# NFCUnlocker.net
KiCad netlist of a schematic drawn in EAGLE
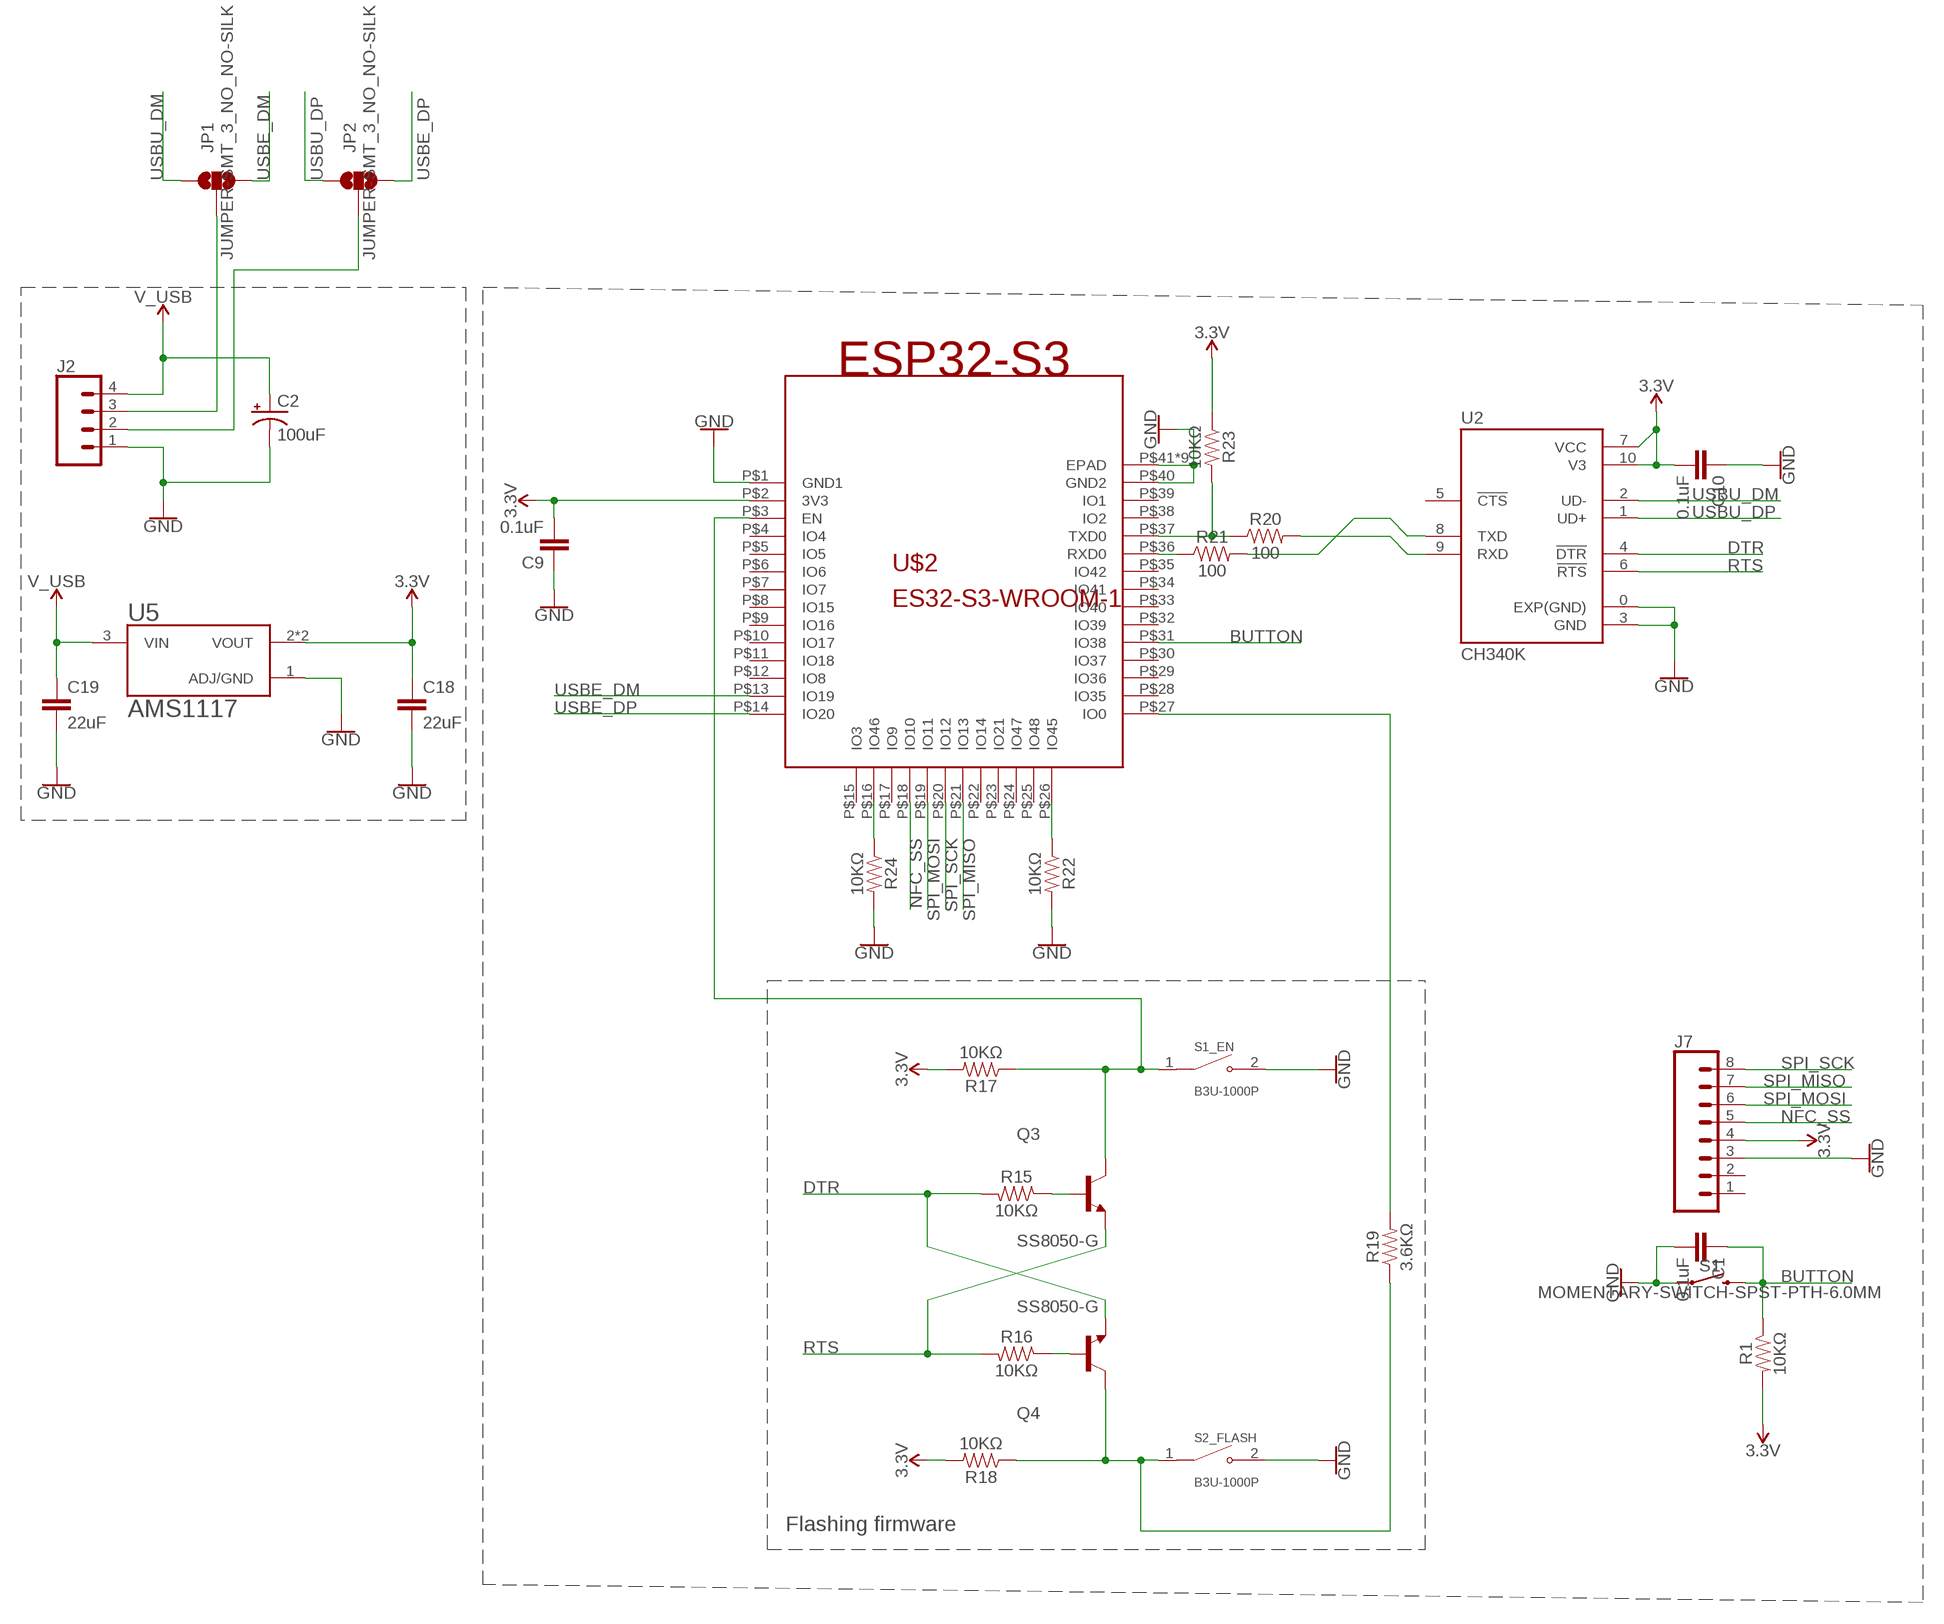
[diagram p0: schematic, sheet 1]

(export (version "E")
  (design (tool "Eeschema 10.0.6"))
  (components
    (comp (ref "C1")
      (value "0.1uF")
      (footprint "eagle-import:0402")
      (libsource (lib "eagle-import") (part "0.1UF-0402-6.3V-10%-X7R"))
    )
    (comp (ref "C2")
      (value "100uF")
      (footprint "eagle-import:CPOL-RADIAL-2.5MM-6.5MM")
      (libsource (lib "eagle-import") (part "100UF-POLAR-RADIAL-2.5MM-25V-20%"))
    )
    (comp (ref "C9")
      (value "0.1uF")
      (footprint "eagle-import:0402")
      (libsource (lib "eagle-import") (part "0.1UF-0402-6.3V-10%-X7R"))
    )
    (comp (ref "C10")
      (value "0.1uF")
      (footprint "eagle-import:0402")
      (libsource (lib "eagle-import") (part "0.1UF-0402-6.3V-10%-X7R"))
    )
    (comp (ref "C18")
      (value "22uF")
      (footprint "eagle-import:1206")
      (libsource (lib "eagle-import") (part "22UF-1206-50V-10%"))
    )
    (comp (ref "C19")
      (value "22uF")
      (footprint "eagle-import:1206")
      (libsource (lib "eagle-import") (part "22UF-1206-50V-10%"))
    )
    (comp (ref "J2")
      (value "CONN_04LONGPADS")
      (footprint "eagle-import:1X04_LONGPADS")
      (libsource (lib "eagle-import") (part "CONN_04LONGPADS"))
    )
    (comp (ref "J7")
      (value "CONN_08LONGPADS")
      (footprint "eagle-import:1X08_LONGPADS")
      (libsource (lib "eagle-import") (part "CONN_08LONGPADS"))
    )
    (comp (ref "JP1")
      (value "JUMPER-SMT_3_NO_NO-SILK")
      (footprint "eagle-import:SMT-JUMPER_3_NO_NO-SILK")
      (libsource (lib "eagle-import") (part "JUMPER-SMT_3_NO_NO-SILK"))
    )
    (comp (ref "JP2")
      (value "JUMPER-SMT_3_NO_NO-SILK")
      (footprint "eagle-import:SMT-JUMPER_3_NO_NO-SILK")
      (libsource (lib "eagle-import") (part "JUMPER-SMT_3_NO_NO-SILK"))
    )
    (comp (ref "Q3")
      (value "SS8050-G")
      (footprint "eagle-import:TRANS_SS8050-G")
      (fields (field (name "MF") "Comchip Technology"))
      (libsource (lib "eagle-import") (part "SS8050-G"))
    )
    (comp (ref "Q4")
      (value "SS8050-G")
      (footprint "eagle-import:TRANS_SS8050-G")
      (fields (field (name "MF") "Comchip Technology"))
      (libsource (lib "eagle-import") (part "SS8050-G"))
    )
    (comp (ref "R1")
      (value "10KΩ")
      (footprint "eagle-import:0402-TIGHT")
      (libsource (lib "eagle-import") (part "10KOHM-0402T-1/16W-1%"))
    )
    (comp (ref "R15")
      (value "10KΩ")
      (footprint "eagle-import:0402-TIGHT")
      (libsource (lib "eagle-import") (part "10KOHM-0402T-1/16W-1%"))
    )
    (comp (ref "R16")
      (value "10KΩ")
      (footprint "eagle-import:0402-TIGHT")
      (libsource (lib "eagle-import") (part "10KOHM-0402T-1/16W-1%"))
    )
    (comp (ref "R17")
      (value "10KΩ")
      (footprint "eagle-import:0402-TIGHT")
      (libsource (lib "eagle-import") (part "10KOHM-0402T-1/16W-1%"))
    )
    (comp (ref "R18")
      (value "10KΩ")
      (footprint "eagle-import:0402-TIGHT")
      (libsource (lib "eagle-import") (part "10KOHM-0402T-1/16W-1%"))
    )
    (comp (ref "R19")
      (value "3.6KΩ")
      (footprint "eagle-import:0402-TIGHT")
      (libsource (lib "eagle-import") (part "10KOHM-0402T-1/16W-1%"))
    )
    (comp (ref "R20")
      (value "100")
      (footprint "eagle-import:0402-TIGHT")
      (libsource (lib "eagle-import") (part "100OHM-0402-TIGHT-1/16W-1%"))
    )
    (comp (ref "R21")
      (value "100")
      (footprint "eagle-import:0402-TIGHT")
      (libsource (lib "eagle-import") (part "100OHM-0402-TIGHT-1/16W-1%"))
    )
    (comp (ref "R22")
      (value "10KΩ")
      (footprint "eagle-import:0402-TIGHT")
      (libsource (lib "eagle-import") (part "10KOHM-0402T-1/16W-1%"))
    )
    (comp (ref "R23")
      (value "10KΩ")
      (footprint "eagle-import:0402-TIGHT")
      (libsource (lib "eagle-import") (part "10KOHM-0402T-1/16W-1%"))
    )
    (comp (ref "R24")
      (value "10KΩ")
      (footprint "eagle-import:0402-TIGHT")
      (libsource (lib "eagle-import") (part "10KOHM-0402T-1/16W-1%"))
    )
    (comp (ref "S1")
      (value "MOMENTARY-SWITCH-SPST-PTH-6.0MM")
      (footprint "eagle-import:TACTILE_SWITCH_PTH_6.0MM")
      (libsource (lib "eagle-import") (part "MOMENTARY-SWITCH-SPST-PTH-6.0MM"))
    )
    (comp (ref "S1_EN")
      (value "B3U-1000P")
      (footprint "eagle-import:SW_B3U-1000P")
      (fields (field (name "MF") "Omron"))
      (libsource (lib "eagle-import") (part "B3U-1000P"))
    )
    (comp (ref "S2_FLASH")
      (value "B3U-1000P")
      (footprint "eagle-import:SW_B3U-1000P")
      (fields (field (name "MF") "Omron"))
      (libsource (lib "eagle-import") (part "B3U-1000P"))
    )
    (comp (ref "U$2")
      (value "ES32-S3-WROOM-1")
      (footprint "eagle-import:ESP32-S3-WROOM-1")
      (libsource (lib "eagle-import") (part "ES32-S3-WROOM-1"))
    )
    (comp (ref "U2")
      (value "CH340K")
      (footprint "eagle-import:SOP100P600X160-11N")
      (fields (field (name "MF") "WCH"))
      (libsource (lib "eagle-import") (part "CH340K"))
    )
    (comp (ref "U5")
      (value "AMS1117")
      (footprint "eagle-import:SOT229P700X180-4N")
      (fields (field (name "MF") "Advanced Monolithic Systems"))
      (libsource (lib "eagle-import") (part "AMS1117"))
    )
  )
  (nets
    (net (code "1") (name "/BUTTON") (class "Default")
      (node (ref "C1") (pin "1") (pinfunction "1_1") (pintype "passive"))
      (node (ref "R1") (pin "1") (pinfunction "1_1") (pintype "passive"))
      (node (ref "S1") (pin "3") (pinfunction "2_3") (pintype "passive"))
      (node (ref "U$2") (pin "P$31") (pinfunction "IO38_P$31") (pintype "bidirectional"))
    )
    (net (code "2") (name "/DTR") (class "Default")
      (node (ref "Q4") (pin "2") (pinfunction "E_2") (pintype "passive"))
      (node (ref "R15") (pin "2") (pinfunction "2_2") (pintype "passive"))
      (node (ref "U2") (pin "4") (pinfunction "~{DTR}_4") (pintype "output"))
    )
    (net (code "3") (name "/NFC_SS") (class "Default")
      (node (ref "J7") (pin "5") (pinfunction "5_5") (pintype "passive"))
      (node (ref "U$2") (pin "P$18") (pinfunction "IO10_P$18") (pintype "bidirectional"))
    )
    (net (code "4") (name "/RTS") (class "Default")
      (node (ref "Q3") (pin "2") (pinfunction "E_2") (pintype "passive"))
      (node (ref "R16") (pin "2") (pinfunction "2_2") (pintype "passive"))
      (node (ref "U2") (pin "6") (pinfunction "~{RTS}_6") (pintype "output"))
    )
    (net (code "5") (name "/SPI_MISO") (class "Default")
      (node (ref "J7") (pin "7") (pinfunction "7_7") (pintype "passive"))
      (node (ref "U$2") (pin "P$21") (pinfunction "IO13_P$21") (pintype "bidirectional"))
    )
    (net (code "6") (name "/SPI_MOSI") (class "Default")
      (node (ref "J7") (pin "6") (pinfunction "6_6") (pintype "passive"))
      (node (ref "U$2") (pin "P$19") (pinfunction "IO11_P$19") (pintype "bidirectional"))
    )
    (net (code "7") (name "/SPI_SCK") (class "Default")
      (node (ref "J7") (pin "8") (pinfunction "8_8") (pintype "passive"))
      (node (ref "U$2") (pin "P$20") (pinfunction "IO12_P$20") (pintype "bidirectional"))
    )
    (net (code "8") (name "/USBE_DM") (class "Default")
      (node (ref "JP1") (pin "3") (pinfunction "3_3") (pintype "passive"))
      (node (ref "U$2") (pin "P$13") (pinfunction "IO19_P$13") (pintype "bidirectional"))
    )
    (net (code "9") (name "/USBE_DP") (class "Default")
      (node (ref "JP2") (pin "3") (pinfunction "3_3") (pintype "passive"))
      (node (ref "U$2") (pin "P$14") (pinfunction "IO20_P$14") (pintype "bidirectional"))
    )
    (net (code "10") (name "/USBU_DM") (class "Default")
      (node (ref "JP1") (pin "1") (pinfunction "1_1") (pintype "passive"))
      (node (ref "U2") (pin "2") (pinfunction "UD-_2") (pintype "bidirectional"))
    )
    (net (code "11") (name "/USBU_DP") (class "Default")
      (node (ref "JP2") (pin "1") (pinfunction "1_1") (pintype "passive"))
      (node (ref "U2") (pin "1") (pinfunction "UD+_1") (pintype "bidirectional"))
    )
    (net (code "12") (name "3.3V") (class "Default")
      (node (ref "C10") (pin "2") (pinfunction "2_2") (pintype "passive"))
      (node (ref "C18") (pin "1") (pinfunction "1_1") (pintype "passive"))
      (node (ref "C9") (pin "2") (pinfunction "2_2") (pintype "passive"))
      (node (ref "J7") (pin "4") (pinfunction "4_4") (pintype "passive"))
      (node (ref "R1") (pin "2") (pinfunction "2_2") (pintype "passive"))
      (node (ref "R17") (pin "2") (pinfunction "2_2") (pintype "passive"))
      (node (ref "R18") (pin "2") (pinfunction "2_2") (pintype "passive"))
      (node (ref "R23") (pin "1") (pinfunction "1_1") (pintype "passive"))
      (node (ref "U$2") (pin "P$2") (pinfunction "3V3_P$2") (pintype "bidirectional"))
      (node (ref "U2") (pin "10") (pinfunction "V3_10") (pintype "power_in"))
      (node (ref "U2") (pin "7") (pinfunction "VCC_7") (pintype "power_in"))
      (node (ref "U5") (pin "2") (pinfunction "VOUT_2") (pintype "output"))
      (node (ref "U5") (pin "4") (pinfunction "VOUT_4") (pintype "output"))
    )
    (net (code "13") (name "GND") (class "Default")
      (node (ref "C1") (pin "2") (pinfunction "2_2") (pintype "passive"))
      (node (ref "C10") (pin "1") (pinfunction "1_1") (pintype "passive"))
      (node (ref "C18") (pin "2") (pinfunction "2_2") (pintype "passive"))
      (node (ref "C19") (pin "2") (pinfunction "2_2") (pintype "passive"))
      (node (ref "C2") (pin "2") (pinfunction "-_2") (pintype "passive"))
      (node (ref "C9") (pin "1") (pinfunction "1_1") (pintype "passive"))
      (node (ref "J2") (pin "1") (pinfunction "1_1") (pintype "passive"))
      (node (ref "J7") (pin "3") (pinfunction "3_3") (pintype "passive"))
      (node (ref "R22") (pin "2") (pinfunction "2_2") (pintype "passive"))
      (node (ref "R24") (pin "2") (pinfunction "2_2") (pintype "passive"))
      (node (ref "S1") (pin "1") (pinfunction "1_1") (pintype "passive"))
      (node (ref "S1_EN") (pin "2") (pinfunction "2_2") (pintype "passive"))
      (node (ref "S2_FLASH") (pin "2") (pinfunction "2_2") (pintype "passive"))
      (node (ref "U$2") (pin "P$1") (pinfunction "GND1_P$1") (pintype "bidirectional"))
      (node (ref "U$2") (pin "P$40") (pinfunction "GND2_P$40") (pintype "bidirectional"))
      (node (ref "U$2") (pin "P$41") (pinfunction "EPAD_P$41") (pintype "bidirectional"))
      (node (ref "U$2") (pin "P$42") (pinfunction "EPAD_P$42") (pintype "bidirectional"))
      (node (ref "U$2") (pin "P$43") (pinfunction "EPAD_P$43") (pintype "bidirectional"))
      (node (ref "U$2") (pin "P$44") (pinfunction "EPAD_P$44") (pintype "bidirectional"))
      (node (ref "U$2") (pin "P$45") (pinfunction "EPAD_P$45") (pintype "bidirectional"))
      (node (ref "U$2") (pin "P$46") (pinfunction "EPAD_P$46") (pintype "bidirectional"))
      (node (ref "U$2") (pin "P$47") (pinfunction "EPAD_P$47") (pintype "bidirectional"))
      (node (ref "U$2") (pin "P$48") (pinfunction "EPAD_P$48") (pintype "bidirectional"))
      (node (ref "U$2") (pin "P$49") (pinfunction "EPAD_P$49") (pintype "bidirectional"))
      (node (ref "U2") (pin "0") (pinfunction "EXP(GND)_0") (pintype "power_in"))
      (node (ref "U2") (pin "3") (pinfunction "GND_3") (pintype "power_in"))
      (node (ref "U5") (pin "1") (pinfunction "ADJ/GND_1") (pintype "power_in"))
    )
    (net (code "14") (name "Net-(J2-Pad2)") (class "Default")
      (node (ref "J2") (pin "2") (pinfunction "2_2") (pintype "passive"))
      (node (ref "JP2") (pin "2") (pinfunction "2_2") (pintype "passive"))
    )
    (net (code "15") (name "Net-(J2-Pad3)") (class "Default")
      (node (ref "J2") (pin "3") (pinfunction "3_3") (pintype "passive"))
      (node (ref "JP1") (pin "2") (pinfunction "2_2") (pintype "passive"))
    )
    (net (code "16") (name "Net-(Q3-B)") (class "Default")
      (node (ref "Q3") (pin "1") (pinfunction "B_1") (pintype "passive"))
      (node (ref "R15") (pin "1") (pinfunction "1_1") (pintype "passive"))
    )
    (net (code "17") (name "Net-(Q3-C)") (class "Default")
      (node (ref "Q3") (pin "3") (pinfunction "C_3") (pintype "passive"))
      (node (ref "R17") (pin "1") (pinfunction "1_1") (pintype "passive"))
      (node (ref "S1_EN") (pin "1") (pinfunction "1_1") (pintype "passive"))
      (node (ref "U$2") (pin "P$3") (pinfunction "EN_P$3") (pintype "bidirectional"))
    )
    (net (code "18") (name "Net-(Q4-B)") (class "Default")
      (node (ref "Q4") (pin "1") (pinfunction "B_1") (pintype "passive"))
      (node (ref "R16") (pin "1") (pinfunction "1_1") (pintype "passive"))
    )
    (net (code "19") (name "Net-(Q4-C)") (class "Default")
      (node (ref "Q4") (pin "3") (pinfunction "C_3") (pintype "passive"))
      (node (ref "R18") (pin "1") (pinfunction "1_1") (pintype "passive"))
      (node (ref "R19") (pin "1") (pinfunction "1_1") (pintype "passive"))
      (node (ref "S2_FLASH") (pin "1") (pinfunction "1_1") (pintype "passive"))
    )
    (net (code "20") (name "Net-(U$2-IO0)") (class "Default")
      (node (ref "R19") (pin "2") (pinfunction "2_2") (pintype "passive"))
      (node (ref "U$2") (pin "P$27") (pinfunction "IO0_P$27") (pintype "bidirectional"))
    )
    (net (code "21") (name "Net-(U$2-IO45)") (class "Default")
      (node (ref "R22") (pin "1") (pinfunction "1_1") (pintype "passive"))
      (node (ref "U$2") (pin "P$26") (pinfunction "IO45_P$26") (pintype "bidirectional"))
    )
    (net (code "22") (name "Net-(U$2-IO46)") (class "Default")
      (node (ref "R24") (pin "1") (pinfunction "1_1") (pintype "passive"))
      (node (ref "U$2") (pin "P$16") (pinfunction "IO46_P$16") (pintype "bidirectional"))
    )
    (net (code "23") (name "Net-(U$2-RXD0)") (class "Default")
      (node (ref "R21") (pin "1") (pinfunction "1_1") (pintype "passive"))
      (node (ref "U$2") (pin "P$36") (pinfunction "RXD0_P$36") (pintype "bidirectional"))
    )
    (net (code "24") (name "Net-(U$2-TXD0)") (class "Default")
      (node (ref "R20") (pin "1") (pinfunction "1_1") (pintype "passive"))
      (node (ref "R23") (pin "2") (pinfunction "2_2") (pintype "passive"))
      (node (ref "U$2") (pin "P$37") (pinfunction "TXD0_P$37") (pintype "bidirectional"))
    )
    (net (code "25") (name "Net-(U2-RXD)") (class "Default")
      (node (ref "R20") (pin "2") (pinfunction "2_2") (pintype "passive"))
      (node (ref "U2") (pin "9") (pinfunction "RXD_9") (pintype "input"))
    )
    (net (code "26") (name "Net-(U2-TXD)") (class "Default")
      (node (ref "R21") (pin "2") (pinfunction "2_2") (pintype "passive"))
      (node (ref "U2") (pin "8") (pinfunction "TXD_8") (pintype "output"))
    )
    (net (code "27") (name "V_USB") (class "Default")
      (node (ref "C19") (pin "1") (pinfunction "1_1") (pintype "passive"))
      (node (ref "C2") (pin "1") (pinfunction "+_1") (pintype "passive"))
      (node (ref "J2") (pin "4") (pinfunction "4_4") (pintype "passive"))
      (node (ref "U5") (pin "3") (pinfunction "VIN_3") (pintype "input"))
    )
    (net (code "28") (name "unconnected-(J7-Pad1)") (class "Default")
      (node (ref "J7") (pin "1") (pinfunction "1_1") (pintype "passive"))
    )
    (net (code "29") (name "unconnected-(J7-Pad2)") (class "Default")
      (node (ref "J7") (pin "2") (pinfunction "2_2") (pintype "passive"))
    )
    (net (code "30") (name "unconnected-(U$2-IO1-PadP$39)") (class "Default")
      (node (ref "U$2") (pin "P$39") (pinfunction "IO1_P$39") (pintype "bidirectional"))
    )
    (net (code "31") (name "unconnected-(U$2-IO2-PadP$38)") (class "Default")
      (node (ref "U$2") (pin "P$38") (pinfunction "IO2_P$38") (pintype "bidirectional"))
    )
    (net (code "32") (name "unconnected-(U$2-IO3-PadP$15)") (class "Default")
      (node (ref "U$2") (pin "P$15") (pinfunction "IO3_P$15") (pintype "bidirectional"))
    )
    (net (code "33") (name "unconnected-(U$2-IO4-PadP$4)") (class "Default")
      (node (ref "U$2") (pin "P$4") (pinfunction "IO4_P$4") (pintype "bidirectional"))
    )
    (net (code "34") (name "unconnected-(U$2-IO5-PadP$5)") (class "Default")
      (node (ref "U$2") (pin "P$5") (pinfunction "IO5_P$5") (pintype "bidirectional"))
    )
    (net (code "35") (name "unconnected-(U$2-IO6-PadP$6)") (class "Default")
      (node (ref "U$2") (pin "P$6") (pinfunction "IO6_P$6") (pintype "bidirectional"))
    )
    (net (code "36") (name "unconnected-(U$2-IO7-PadP$7)") (class "Default")
      (node (ref "U$2") (pin "P$7") (pinfunction "IO7_P$7") (pintype "bidirectional"))
    )
    (net (code "37") (name "unconnected-(U$2-IO8-PadP$12)") (class "Default")
      (node (ref "U$2") (pin "P$12") (pinfunction "IO8_P$12") (pintype "bidirectional"))
    )
    (net (code "38") (name "unconnected-(U$2-IO9-PadP$17)") (class "Default")
      (node (ref "U$2") (pin "P$17") (pinfunction "IO9_P$17") (pintype "bidirectional"))
    )
    (net (code "39") (name "unconnected-(U$2-IO14-PadP$22)") (class "Default")
      (node (ref "U$2") (pin "P$22") (pinfunction "IO14_P$22") (pintype "bidirectional"))
    )
    (net (code "40") (name "unconnected-(U$2-IO15-PadP$8)") (class "Default")
      (node (ref "U$2") (pin "P$8") (pinfunction "IO15_P$8") (pintype "bidirectional"))
    )
    (net (code "41") (name "unconnected-(U$2-IO16-PadP$9)") (class "Default")
      (node (ref "U$2") (pin "P$9") (pinfunction "IO16_P$9") (pintype "bidirectional"))
    )
    (net (code "42") (name "unconnected-(U$2-IO17-PadP$10)") (class "Default")
      (node (ref "U$2") (pin "P$10") (pinfunction "IO17_P$10") (pintype "bidirectional"))
    )
    (net (code "43") (name "unconnected-(U$2-IO18-PadP$11)") (class "Default")
      (node (ref "U$2") (pin "P$11") (pinfunction "IO18_P$11") (pintype "bidirectional"))
    )
    (net (code "44") (name "unconnected-(U$2-IO21-PadP$23)") (class "Default")
      (node (ref "U$2") (pin "P$23") (pinfunction "IO21_P$23") (pintype "bidirectional"))
    )
    (net (code "45") (name "unconnected-(U$2-IO35-PadP$28)") (class "Default")
      (node (ref "U$2") (pin "P$28") (pinfunction "IO35_P$28") (pintype "bidirectional"))
    )
    (net (code "46") (name "unconnected-(U$2-IO36-PadP$29)") (class "Default")
      (node (ref "U$2") (pin "P$29") (pinfunction "IO36_P$29") (pintype "bidirectional"))
    )
    (net (code "47") (name "unconnected-(U$2-IO37-PadP$30)") (class "Default")
      (node (ref "U$2") (pin "P$30") (pinfunction "IO37_P$30") (pintype "bidirectional"))
    )
    (net (code "48") (name "unconnected-(U$2-IO39-PadP$32)") (class "Default")
      (node (ref "U$2") (pin "P$32") (pinfunction "IO39_P$32") (pintype "bidirectional"))
    )
    (net (code "49") (name "unconnected-(U$2-IO40-PadP$33)") (class "Default")
      (node (ref "U$2") (pin "P$33") (pinfunction "IO40_P$33") (pintype "bidirectional"))
    )
    (net (code "50") (name "unconnected-(U$2-IO41-PadP$34)") (class "Default")
      (node (ref "U$2") (pin "P$34") (pinfunction "IO41_P$34") (pintype "bidirectional"))
    )
    (net (code "51") (name "unconnected-(U$2-IO42-PadP$35)") (class "Default")
      (node (ref "U$2") (pin "P$35") (pinfunction "IO42_P$35") (pintype "bidirectional"))
    )
    (net (code "52") (name "unconnected-(U$2-IO47-PadP$24)") (class "Default")
      (node (ref "U$2") (pin "P$24") (pinfunction "IO47_P$24") (pintype "bidirectional"))
    )
    (net (code "53") (name "unconnected-(U$2-IO48-PadP$25)") (class "Default")
      (node (ref "U$2") (pin "P$25") (pinfunction "IO48_P$25") (pintype "bidirectional"))
    )
    (net (code "54") (name "unconnected-(U2-~{CTS}-Pad5)") (class "Default")
      (node (ref "U2") (pin "5") (pinfunction "~{CTS}_5") (pintype "input"))
    )
  )
)
